# Power.net
KiCad netlist of a schematic drawn in Altium Designer
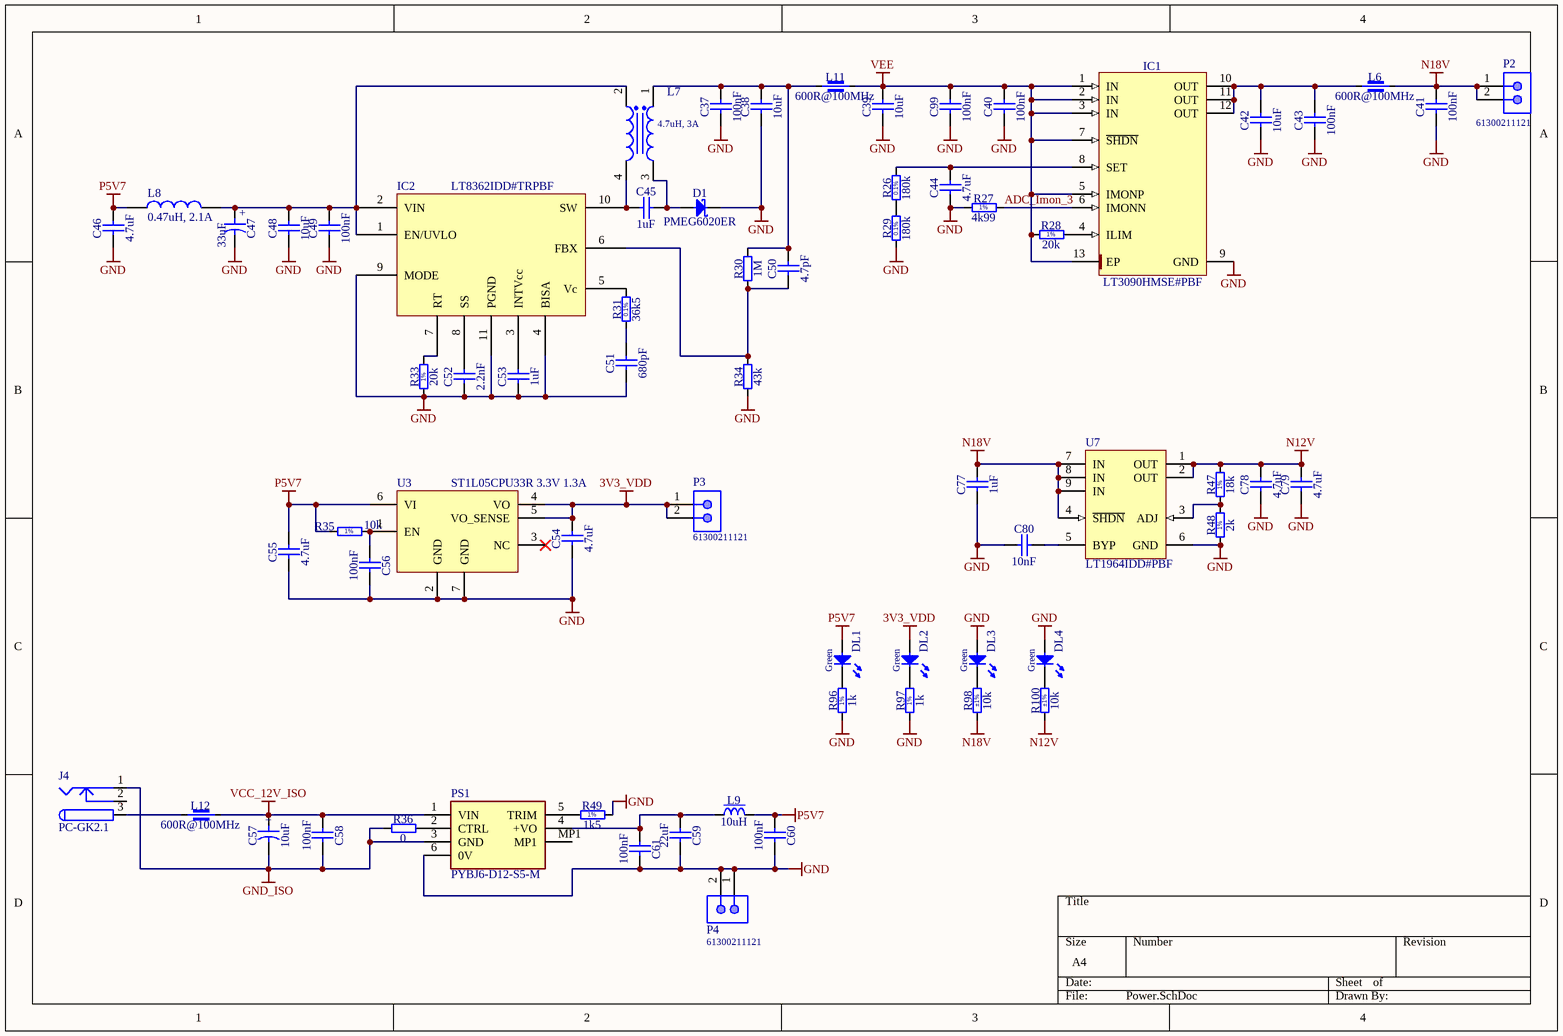
[diagram p0: Power.SchDoc]

(export (version "E")
  (design (tool "Eeschema 10.0.6"))
  (components
    (comp (ref "C37")
      (value "100nF")
      (footprint "CAPC1608X87N")
      (description "Non-polarised capacitor")
      (fields
        (field (name "PART NUMBER") "CC0603_100NF_50V_10%_X5R")
        (field (name "VOLTAGE") "50V")
        (field (name "AUTHOR") "CERN DEM MR")
      )
      (libsource (lib "Capacitors") (part "Capacitor - non polarized"))
    )
    (comp (ref "C38")
      (value "10uF")
      (footprint "CAPC3216X190N")
      (description "Non-polarised capacitor")
      (fields
        (field (name "PART NUMBER") "CC1206_10UF_35V_10%_X7R_YUDEN_GMJ316BB7106KLHT")
        (field (name "VOLTAGE") "35V")
        (field (name "AUTHOR") "CERN DEM BC")
      )
      (libsource (lib "Capacitors") (part "Capacitor - non polarized"))
    )
    (comp (ref "C39")
      (value "10uF")
      (footprint "CAPC3216X190N")
      (description "Non-polarised capacitor")
      (fields
        (field (name "PART NUMBER") "CC1206_10UF_35V_10%_X7R_YUDEN_GMJ316BB7106KLHT")
        (field (name "VOLTAGE") "35V")
        (field (name "AUTHOR") "CERN DEM BC")
      )
      (libsource (lib "Capacitors") (part "Capacitor - non polarized"))
    )
    (comp (ref "C40")
      (value "100nF")
      (footprint "CAPC1608X87N")
      (description "Non-polarised capacitor")
      (fields
        (field (name "PART NUMBER") "CC0603_100NF_50V_10%_X5R")
        (field (name "VOLTAGE") "50V")
        (field (name "AUTHOR") "CERN DEM MR")
      )
      (libsource (lib "Capacitors") (part "Capacitor - non polarized"))
    )
    (comp (ref "C41")
      (value "100nF")
      (footprint "CAPC1608X87N")
      (description "Non-polarised capacitor")
      (fields
        (field (name "PART NUMBER") "CC0603_100NF_50V_10%_X5R")
        (field (name "VOLTAGE") "50V")
        (field (name "AUTHOR") "CERN DEM MR")
      )
      (libsource (lib "Capacitors") (part "Capacitor - non polarized"))
    )
    (comp (ref "C42")
      (value "10uF")
      (footprint "CAPC3216X190N")
      (description "Non-polarised capacitor")
      (fields
        (field (name "PART NUMBER") "CC1206_10UF_35V_10%_X7R_YUDEN_GMJ316BB7106KLHT")
        (field (name "VOLTAGE") "35V")
        (field (name "AUTHOR") "CERN DEM BC")
      )
      (libsource (lib "Capacitors") (part "Capacitor - non polarized"))
    )
    (comp (ref "C43")
      (value "100nF")
      (footprint "CAPC1608X87N")
      (description "Non-polarised capacitor")
      (fields
        (field (name "PART NUMBER") "CC0603_100NF_50V_10%_X5R")
        (field (name "VOLTAGE") "50V")
        (field (name "AUTHOR") "CERN DEM MR")
      )
      (libsource (lib "Capacitors") (part "Capacitor - non polarized"))
    )
    (comp (ref "C44")
      (value "4.7uF")
      (footprint "CAPC1608X90N")
      (description "Non-polarised capacitor")
      (fields
        (field (name "PART NUMBER") "CC0603_4.7UF_25V_10%_X5R")
        (field (name "VOLTAGE") "25V")
        (field (name "AUTHOR") "CERN DEM JLC")
      )
      (libsource (lib "Capacitors") (part "Capacitor - non polarized"))
    )
    (comp (ref "C45")
      (value "1uF")
      (footprint "CAPC3216X140N")
      (description "Non-polarised capacitor")
      (fields
        (field (name "PART NUMBER") "CC1206_1UF_100V_10%_X7R")
        (field (name "VOLTAGE") "100V")
        (field (name "AUTHOR") "CERN DEM BC")
      )
      (libsource (lib "Capacitors") (part "Capacitor - non polarized"))
    )
    (comp (ref "C46")
      (value "4.7uF")
      (footprint "CAPC1608X90N")
      (description "Non-polarised capacitor")
      (fields
        (field (name "PART NUMBER") "CC0603_4.7UF_25V_10%_X5R")
        (field (name "VOLTAGE") "25V")
        (field (name "AUTHOR") "CERN DEM JLC")
      )
      (libsource (lib "Capacitors") (part "Capacitor - non polarized"))
    )
    (comp (ref "C47")
      (value "33uF")
      (footprint "CAPAE660X540N")
      (description "Polarised capacitor")
      (fields
        (field (name "PART NUMBER") "CAE660-540_33UF_35V_20%")
        (field (name "VOLTAGE") "35V")
        (field (name "AUTHOR") "CERN DEM JLC")
      )
      (libsource (lib "") (part "Capacitor - polarized_1"))
    )
    (comp (ref "C48")
      (value "10uF")
      (footprint "CAPC3216X190N")
      (description "Non-polarised capacitor")
      (fields
        (field (name "PART NUMBER") "CC1206_10UF_35V_10%_X7R_YUDEN_GMJ316BB7106KLHT")
        (field (name "VOLTAGE") "35V")
        (field (name "AUTHOR") "CERN DEM BC")
      )
      (libsource (lib "Capacitors") (part "Capacitor - non polarized"))
    )
    (comp (ref "C49")
      (value "100nF")
      (footprint "CAPC1608X87N")
      (description "Non-polarised capacitor")
      (fields
        (field (name "PART NUMBER") "CC0603_100NF_50V_10%_X5R")
        (field (name "VOLTAGE") "50V")
        (field (name "AUTHOR") "CERN DEM MR")
      )
      (libsource (lib "Capacitors") (part "Capacitor - non polarized"))
    )
    (comp (ref "C50")
      (value "4.7pF")
      (footprint "CAPC1005X55N")
      (description "Non-polarised capacitor")
      (fields
        (field (name "PART NUMBER") "CC0402_4.7PF_50V_0.25PF_C0G")
        (field (name "VOLTAGE") "50V")
        (field (name "AUTHOR") "CERN DEM JLC")
      )
      (libsource (lib "Capacitors") (part "Capacitor - non polarized"))
    )
    (comp (ref "C51")
      (value "680pF")
      (footprint "CAPC1005X55N")
      (description "Non-polarised capacitor")
      (fields
        (field (name "PART NUMBER") "CC0402_680PF_50V_5%_X7R")
        (field (name "VOLTAGE") "50V")
        (field (name "AUTHOR") "CERN DEM JLC")
      )
      (libsource (lib "Capacitors") (part "Capacitor - non polarized"))
    )
    (comp (ref "C52")
      (value "2.2nF")
      (footprint "CAPC1005X55N")
      (description "Non-polarised capacitor")
      (fields
        (field (name "PART NUMBER") "CC0402_2.2NF_50V_10%_X7R")
        (field (name "VOLTAGE") "50V")
        (field (name "AUTHOR") "CERN DEM JLC")
      )
      (libsource (lib "Capacitors") (part "Capacitor - non polarized"))
    )
    (comp (ref "C53")
      (value "1uF")
      (footprint "CAPC1608X87N")
      (description "Non-polarised capacitor")
      (fields
        (field (name "PART NUMBER") "CC0603_1UF_16V_10%_X7R")
        (field (name "VOLTAGE") "16V")
        (field (name "AUTHOR") "CERN DEM JLC")
      )
      (libsource (lib "Capacitors") (part "Capacitor - non polarized"))
    )
    (comp (ref "C54")
      (value "4.7uF")
      (footprint "CAPC1709X95N")
      (description "Non-polarised capacitor")
      (fields
        (field (name "PART NUMBER") "CC0603_4.7UF_16V_10%_X5R")
        (field (name "VOLTAGE") "16V")
        (field (name "AUTHOR") "CERN DEM JLC")
      )
      (libsource (lib "Capacitors") (part "Capacitor - non polarized"))
    )
    (comp (ref "C55")
      (value "4.7uF")
      (footprint "CAPC1709X95N")
      (description "Non-polarised capacitor")
      (fields
        (field (name "PART NUMBER") "CC0603_4.7UF_16V_10%_X5R")
        (field (name "VOLTAGE") "16V")
        (field (name "AUTHOR") "CERN DEM JLC")
      )
      (libsource (lib "Capacitors") (part "Capacitor - non polarized"))
    )
    (comp (ref "C56")
      (value "100nF")
      (footprint "CAPC1005X55N")
      (description "Non-polarised capacitor")
      (fields
        (field (name "PART NUMBER") "CC0402_100NF_16V_10%_X5R")
        (field (name "VOLTAGE") "16V")
        (field (name "AUTHOR") "CERN DEM JLC")
      )
      (libsource (lib "Capacitors") (part "Capacitor - non polarized"))
    )
    (comp (ref "C57")
      (value "10uF")
      (footprint "CAPAE430X540N")
      (description "Polarised capacitor")
      (fields
        (field (name "PART NUMBER") "CAE430-540_10UF_16V_20%")
        (field (name "VOLTAGE") "16V")
        (field (name "AUTHOR") "CERN DEM JLC")
      )
      (libsource (lib "Capacitors") (part "Capacitor - polarized"))
    )
    (comp (ref "C58")
      (value "100nF")
      (footprint "CAPC1005X55N")
      (description "Non-polarised capacitor")
      (fields
        (field (name "PART NUMBER") "CC0402_100NF_16V_10%_X5R")
        (field (name "VOLTAGE") "16V")
        (field (name "AUTHOR") "CERN DEM JLC")
      )
      (libsource (lib "Capacitors") (part "Capacitor - non polarized"))
    )
    (comp (ref "C59")
      (value "22uF")
      (footprint "CAPC2012X135N")
      (description "Non-polarised capacitor")
      (fields
        (field (name "PART NUMBER") "CC0805_22UF_16V_10%_X5R")
        (field (name "VOLTAGE") "16V")
        (field (name "AUTHOR") "CERN DEM JLC")
      )
      (libsource (lib "Capacitors") (part "Capacitor - non polarized"))
    )
    (comp (ref "C60")
      (value "100nF")
      (footprint "CAPC1005X55N")
      (description "Non-polarised capacitor")
      (fields
        (field (name "PART NUMBER") "CC0402_100NF_16V_10%_X5R")
        (field (name "VOLTAGE") "16V")
        (field (name "AUTHOR") "CERN DEM JLC")
      )
      (libsource (lib "Capacitors") (part "Capacitor - non polarized"))
    )
    (comp (ref "C61")
      (value "100nF")
      (footprint "CAPC1005X55N")
      (description "Non-polarised capacitor")
      (fields
        (field (name "PART NUMBER") "CC0402_100NF_16V_10%_X5R")
        (field (name "VOLTAGE") "16V")
        (field (name "AUTHOR") "CERN DEM JLC")
      )
      (libsource (lib "Capacitors") (part "Capacitor - non polarized"))
    )
    (comp (ref "C77")
      (value "1uF")
      (footprint "CAPC1608X87N")
      (description "Non-polarised capacitor")
      (fields
        (field (name "PART NUMBER") "CC0603_1UF_25V_10%_X7R")
        (field (name "VOLTAGE") "25V")
        (field (name "AUTHOR") "CERN DEM JLC")
      )
      (libsource (lib "Capacitors") (part "Capacitor - non polarized"))
    )
    (comp (ref "C78")
      (value "4.7uF")
      (footprint "CAPC1709X95N")
      (description "Non-polarised capacitor")
      (fields
        (field (name "PART NUMBER") "CC0603_4.7UF_16V_10%_X5R")
        (field (name "VOLTAGE") "16V")
        (field (name "AUTHOR") "CERN DEM JLC")
      )
      (libsource (lib "Capacitors") (part "Capacitor - non polarized"))
    )
    (comp (ref "C79")
      (value "4.7uF")
      (footprint "CAPC1709X95N")
      (description "Non-polarised capacitor")
      (fields
        (field (name "PART NUMBER") "CC0603_4.7UF_16V_10%_X5R")
        (field (name "VOLTAGE") "16V")
        (field (name "AUTHOR") "CERN DEM JLC")
      )
      (libsource (lib "Capacitors") (part "Capacitor - non polarized"))
    )
    (comp (ref "C80")
      (value "10nF")
      (footprint "CAPC1005X55N")
      (description "Non-polarised capacitor")
      (fields
        (field (name "PART NUMBER") "CC0402_10NF_16V_10%_X7R")
        (field (name "VOLTAGE") "16V")
        (field (name "AUTHOR") "CERN DEM JLC")
      )
      (libsource (lib "Capacitors") (part "Capacitor - non polarized"))
    )
    (comp (ref "C99")
      (value "100nF")
      (footprint "CAPC1608X87N")
      (description "Non-polarised capacitor")
      (fields
        (field (name "PART NUMBER") "CC0603_100NF_50V_10%_X5R")
        (field (name "VOLTAGE") "50V")
        (field (name "AUTHOR") "CERN DEM MR")
      )
      (libsource (lib "Capacitors") (part "Capacitor - non polarized"))
    )
    (comp (ref "D1")
      (value "PMEG6020ER")
      (footprint "SODFL3517X110N")
      (description "Schottky Diode")
      (fields
        (field (name "VOLTAGE") "60V")
        (field (name "POWER") "2A")
        (field (name "AUTHOR") "CERN DEM JMW")
      )
      (libsource (lib "ICs And Semiconductors") (part "Diode Schottky"))
    )
    (comp (ref "DL1")
      (value "Green")
      (footprint "LED_OSRAM_LGL29K")
      (description "LED Green 1C 2A")
      (fields
        (field (name "PART NUMBER") "LED_OSRAM_LG L29K-G2J1-24-Z")
        (field (name "MANUFACTURER") "OSRAM")
        (field (name "AUTHOR") "CERN DEM JLC")
      )
      (libsource (lib "ICs And Semiconductors") (part "LED Green 1C 2A"))
    )
    (comp (ref "DL2")
      (value "Green")
      (footprint "LED_OSRAM_LGL29K")
      (description "LED Green 1C 2A")
      (fields
        (field (name "PART NUMBER") "LED_OSRAM_LG L29K-G2J1-24-Z")
        (field (name "MANUFACTURER") "OSRAM")
        (field (name "AUTHOR") "CERN DEM JLC")
      )
      (libsource (lib "ICs And Semiconductors") (part "LED Green 1C 2A"))
    )
    (comp (ref "DL3")
      (value "Green")
      (footprint "LED_OSRAM_LGL29K")
      (description "LED Green 1C 2A")
      (fields
        (field (name "PART NUMBER") "LED_OSRAM_LG L29K-G2J1-24-Z")
        (field (name "MANUFACTURER") "OSRAM")
        (field (name "AUTHOR") "CERN DEM JLC")
      )
      (libsource (lib "ICs And Semiconductors") (part "LED Green 1C 2A"))
    )
    (comp (ref "DL4")
      (value "Green")
      (footprint "LED_OSRAM_LGL29K")
      (description "LED Green 1C 2A")
      (fields
        (field (name "PART NUMBER") "LED_OSRAM_LG L29K-G2J1-24-Z")
        (field (name "MANUFACTURER") "OSRAM")
        (field (name "AUTHOR") "CERN DEM JLC")
      )
      (libsource (lib "ICs And Semiconductors") (part "LED Green 1C 2A"))
    )
    (comp (ref "IC1")
      (value "LT3090HMSE#PBF")
      (footprint "SOP65P490X110-13N-R175X294")
      (description "–36V, 600mA Negative Linear Regulator with Programmable Current Limit")
      (fields (field (name "MANUFACTURER") "LINEAR TECHNOLOGY") (field (name "AUTHOR") "CERN DEM JLC"))
      (libsource (lib "ICs And Semiconductors") (part "LT3090HMSE#PBF"))
    )
    (comp (ref "IC2")
      (value "LT8362IDD#TRPBF")
      (footprint "SON50P300X300X80-11N-R160X240")
      (libsource (lib "MG_lib") (part "LT8362IDD#TRPBF"))
    )
    (comp (ref "J4")
      (value "PC-GK2.1")
      (footprint "DC2020")
      (description "Low Voltage Power Supply Connector (maritex)")
      (fields (field (name "PUBLISHER") "Altium Limited"))
      (libsource (lib "LIBRARY_SCH") (part "CON_DC_JACK_TH"))
    )
    (comp (ref "L6")
      (value "600R@100MHz")
      (footprint "INDC2012X110N")
      (fields
        (field (name "PART NUMBER") "IND0805_WURTH_742792040")
        (field (name "POWER") "2A")
        (field (name "TOLERANCE") "±25%")
        (field (name "AUTHOR") "CERN DEM JLC")
      )
      (libsource (lib "Inductors & Transformers") (part "Ferrite Bead"))
    )
    (comp (ref "L7")
      (value "4.7uH, 3A")
      (footprint "WE-DD_1260")
      (description "WE-DD SMT Shielded Coupled Inductor, size 1260, 4.7uH, 3A")
      (fields
        (field (name "MANUFACTURER") "Wurth Elektronik")
        (field (name "MANUFACTURER PART NUMBER") "744871004")
      )
      (libsource (lib "744871470_Altium_WE-DD_rev20a") (part "744871004"))
    )
    (comp (ref "L8")
      (value "0.47uH, 2.1A")
      (footprint "WE-PMI_0806_H1")
      (description "WE-PMI Power Multilayer Inductor, size 0806, 0.47uH, 2.1A")
      (fields
        (field (name "MANUFACTURER") "Wurth Elektronik")
        (field (name "MANUFACTURER PART NUMBER") "74479876147")
      )
      (libsource (lib "Altium_WE-PMI_rev20a") (part "74479876147"))
    )
    (comp (ref "L9")
      (value "10uH")
      (footprint "IND_MURATA-PS_8400")
      (description "Inductor With Core")
      (fields
        (field (name "PART NUMBER") "IND_10UH_10%_MURATA-PS_8400")
        (field (name "POWER") "950mA")
        (field (name "AUTHOR") "CERN DEM JLC")
      )
      (libsource (lib "Inductors & Transformers") (part "Inductor With Magnetic core"))
    )
    (comp (ref "L11")
      (value "600R@100MHz")
      (footprint "INDC2012X110N")
      (fields
        (field (name "PART NUMBER") "IND0805_WURTH_742792040")
        (field (name "POWER") "2A")
        (field (name "TOLERANCE") "±25%")
        (field (name "AUTHOR") "CERN DEM JLC")
      )
      (libsource (lib "Inductors & Transformers") (part "Ferrite Bead"))
    )
    (comp (ref "L12")
      (value "600R@100MHz")
      (footprint "INDC2012X110N")
      (fields
        (field (name "PART NUMBER") "IND0805_WURTH_742792040")
        (field (name "POWER") "2A")
        (field (name "TOLERANCE") "±25%")
        (field (name "AUTHOR") "CERN DEM JLC")
      )
      (libsource (lib "Inductors & Transformers") (part "Ferrite Bead"))
    )
    (comp (ref "P2")
      (value "61300211121")
      (footprint "61300211121")
      (description "WR-PHD Pin Header, THT, pitch 2.54mm, Single Row, Vertical, 2p")
      (fields (field (name "MANUFACTURER") "Wurth Elektronik"))
      (libsource (lib "o155175v243 Altium_WR-PHD (rev20a)") (part "61300211121"))
    )
    (comp (ref "P3")
      (value "61300211121")
      (footprint "61300211121")
      (description "WR-PHD Pin Header, THT, pitch 2.54mm, Single Row, Vertical, 2p")
      (fields (field (name "MANUFACTURER") "Wurth Elektronik"))
      (libsource (lib "o155175v243 Altium_WR-PHD (rev20a)") (part "61300211121"))
    )
    (comp (ref "P4")
      (value "61300211121")
      (footprint "61300211121")
      (description "WR-PHD Pin Header, THT, pitch 2.54mm, Single Row, Vertical, 2p")
      (fields (field (name "MANUFACTURER") "Wurth Elektronik"))
      (libsource (lib "o155175v243 Altium_WR-PHD (rev20a)") (part "61300211121"))
    )
    (comp (ref "PS1")
      (value "PYBJ6-D12-S5-M")
      (footprint "PYBJ6D12S12M")
      (description "Power Supply")
      (fields (field (name "MANUFACTURER_PART_NUMBER") "PYBJ6-D12-S12-M"))
      (libsource (lib "*") (part "PYBJ6-D12-S12-M"))
    )
    (comp (ref "R26")
      (value "180k")
      (footprint "RESC3216X65N")
      (description "Resistor - 0.1%")
      (fields
        (field (name "PART NUMBER") "R1206_180K_0.1%_0.25W_25PPM")
        (field (name "POWER") "0.25W")
        (field (name "AUTHOR") "CERN DEM JLC")
      )
      (libsource (lib "Resistors") (part "Resistor - 0.1%"))
    )
    (comp (ref "R27")
      (value "4k99")
      (footprint "RESC1608X55N")
      (description "Resistor - 1%")
      (fields
        (field (name "PART NUMBER") "R0603_4K99_1%_0.063W_50PPM")
        (field (name "POWER") "0.063W")
        (field (name "AUTHOR") "CERN DEM JLC")
      )
      (libsource (lib "Resistors") (part "Resistor - 1%"))
    )
    (comp (ref "R28")
      (value "20k")
      (footprint "RESC1005X40N")
      (description "Resistor - 1%")
      (fields
        (field (name "PART NUMBER") "R0402_20K_1%_0.0625W_100PPM")
        (field (name "POWER") "0.0625W")
        (field (name "AUTHOR") "CERN DEM JLC")
      )
      (libsource (lib "") (part "Resistor - 1%_1"))
    )
    (comp (ref "R29")
      (value "180k")
      (footprint "RESC3216X65N")
      (description "Resistor - 0.1%")
      (fields
        (field (name "PART NUMBER") "R1206_180K_0.1%_0.25W_25PPM")
        (field (name "POWER") "0.25W")
        (field (name "AUTHOR") "CERN DEM JLC")
      )
      (libsource (lib "Resistors") (part "Resistor - 0.1%"))
    )
    (comp (ref "R30")
      (value "1M")
      (footprint "RESC1005X40N")
      (description "Resistor - 1%")
      (fields
        (field (name "PART NUMBER") "R0402_1M_1%_0.0625W_100PPM")
        (field (name "POWER") "0.0625W")
        (field (name "AUTHOR") "CERN DEM JLC")
      )
      (libsource (lib "") (part "Resistor - 1%_1"))
    )
    (comp (ref "R31")
      (value "36k5")
      (footprint "RESC1608X55N")
      (description "Resistor - 0.1%")
      (fields
        (field (name "PART NUMBER") "R0603_36K5_0.1%_0.063W_10PPM")
        (field (name "POWER") "0.063W")
        (field (name "AUTHOR") "CERN DEM JLC")
      )
      (libsource (lib "Resistors") (part "Resistor - 0.1%"))
    )
    (comp (ref "R33")
      (value "20k")
      (footprint "RESC1005X40N")
      (description "Resistor - 1%")
      (fields
        (field (name "PART NUMBER") "R0402_20K_1%_0.0625W_100PPM")
        (field (name "POWER") "0.0625W")
        (field (name "AUTHOR") "CERN DEM JLC")
      )
      (libsource (lib "") (part "Resistor - 1%_1"))
    )
    (comp (ref "R34")
      (value "43k")
      (footprint "RESC1005X40N")
      (description "Resistor - 1%")
      (fields
        (field (name "PART NUMBER") "R0402_43K_1%_0.0625W_100PPM")
        (field (name "POWER") "0.0625W")
        (field (name "AUTHOR") "CERN DEM JLC")
      )
      (libsource (lib "") (part "Resistor - 1%_1"))
    )
    (comp (ref "R35")
      (value "10k")
      (footprint "RESC1005X40N")
      (description "Resistor - 1%")
      (fields
        (field (name "PART NUMBER") "R0402_10K_1%_0.0625W_100PPM")
        (field (name "POWER") "0.0625W")
        (field (name "AUTHOR") "CERN DEM JLC")
      )
      (libsource (lib "") (part "Resistor - 1%_1"))
    )
    (comp (ref "R36")
      (value "0")
      (footprint "RESC1608X55N")
      (description "Resistor")
      (fields
        (field (name "PART NUMBER") "R0603_0R_JUMPER")
        (field (name "MANUFACTURER") "GENERIC")
        (field (name "AUTHOR") "CERN DEM JLC")
      )
      (libsource (lib "Resistors") (part "Resistor"))
    )
    (comp (ref "R47")
      (value "18k")
      (footprint "RESC1005X40N")
      (description "Resistor - 1%")
      (fields
        (field (name "PART NUMBER") "R0402_18K_1%_0.0625W_100PPM")
        (field (name "POWER") "0.0625W")
        (field (name "AUTHOR") "CERN DEM JLC")
      )
      (libsource (lib "") (part "Resistor - 1%_1"))
    )
    (comp (ref "R48")
      (value "2k")
      (footprint "RESC1005X40N")
      (description "Resistor - 1%")
      (fields
        (field (name "PART NUMBER") "R0402_2K_1%_0.0625W_100PPM")
        (field (name "POWER") "0.0625W")
        (field (name "AUTHOR") "CERN DEM JLC")
      )
      (libsource (lib "") (part "Resistor - 1%_1"))
    )
    (comp (ref "R49")
      (value "1k5")
      (footprint "RESC1005X40N")
      (description "Resistor - 1%")
      (fields
        (field (name "PART NUMBER") "R0402_1K5_1%_0.0625W_100PPM")
        (field (name "POWER") "0.0625W")
        (field (name "AUTHOR") "CERN DEM JLC")
      )
      (libsource (lib "") (part "Resistor - 1%_1"))
    )
    (comp (ref "R96")
      (value "1k")
      (footprint "RESC1005X40N")
      (description "Resistor - 1%")
      (fields
        (field (name "PART NUMBER") "R0402_1K_1%_0.0625W_100PPM")
        (field (name "POWER") "0.0625W")
        (field (name "AUTHOR") "CERN DEM JLC")
      )
      (libsource (lib "") (part "Resistor - 1%_1"))
    )
    (comp (ref "R97")
      (value "1k")
      (footprint "RESC1005X40N")
      (description "Resistor - 1%")
      (fields
        (field (name "PART NUMBER") "R0402_1K_1%_0.0625W_100PPM")
        (field (name "POWER") "0.0625W")
        (field (name "AUTHOR") "CERN DEM JLC")
      )
      (libsource (lib "") (part "Resistor - 1%_1"))
    )
    (comp (ref "R98")
      (value "10k")
      (footprint "RESC1005X40N")
      (description "Resistor - 1%")
      (fields
        (field (name "TOLERANCE") "±1%")
        (field (name "PART NUMBER") "R0402_10K_1%_0.0625W_100PPM")
        (field (name "POWER") "0.0625W")
        (field (name "AUTHOR") "CERN DEM JLC")
      )
      (libsource (lib "") (part "Resistor - 1%_1"))
    )
    (comp (ref "R100")
      (value "10k")
      (footprint "RESC1005X40N")
      (description "Resistor - 1%")
      (fields
        (field (name "TOLERANCE") "±1%")
        (field (name "PART NUMBER") "R0402_10K_1%_0.0625W_100PPM")
        (field (name "POWER") "0.0625W")
        (field (name "AUTHOR") "CERN DEM JLC")
      )
      (libsource (lib "") (part "Resistor - 1%_1"))
    )
    (comp (ref "U3")
      (value "ST1L05CPU33R 3.3V 1.3A")
      (footprint "SON95P300X300X80-7N-R160X240")
      (description "LDO, 3.3V, 1.3A, Very low quiescent current BiCMOS voltage regulator")
      (fields
        (field (name "INTERNAL_PART_NUMBER") "MCD-01025")
        (field (name "MANUFACTURER_PART_NUMBER") "ST1L05CPU33R")
        (field (name "PROVIDED_BY") "SUBCO with ST control")
      )
      (libsource (lib "MCD_PARTS_database") (part "ST1L05CPU33R"))
    )
    (comp (ref "U7")
      (value "LT1964IDD#PBF")
      (footprint "LT-DD-8_V")
      (fields (field (name "MANUFACTURER") "Linear Technology"))
      (libsource (lib "Altium Content Vault") (part "LT-LT1964-DD-8"))
    )
  )
  (nets
    (net (code "1") (name "/ADC_Imon_3") (class "Default")
      (node (ref "IC1") (pin "6") (pinfunction "IMONN_6") (pintype "input"))
      (node (ref "R27") (pin "2") (pinfunction "2_2") (pintype "passive"))
    )
    (net (code "2") (name "3V3_VDD") (class "Default")
      (node (ref "C54") (pin "2") (pinfunction "2_2") (pintype "passive"))
      (node (ref "DL2") (pin "2") (pinfunction "A_2") (pintype "passive"))
      (node (ref "P3") (pin "1") (pinfunction "1_1") (pintype "passive"))
      (node (ref "P3") (pin "2") (pinfunction "2_2") (pintype "passive"))
      (node (ref "U3") (pin "4") (pinfunction "VO_4") (pintype "passive"))
      (node (ref "U3") (pin "5") (pinfunction "VO_SENSE_5") (pintype "passive"))
    )
    (net (code "3") (name "GND") (class "Default")
      (node (ref "C37") (pin "1") (pinfunction "1_1") (pintype "passive"))
      (node (ref "C38") (pin "1") (pinfunction "1_1") (pintype "passive"))
      (node (ref "C39") (pin "1") (pinfunction "1_1") (pintype "passive"))
      (node (ref "C40") (pin "1") (pinfunction "1_1") (pintype "passive"))
      (node (ref "C41") (pin "1") (pinfunction "1_1") (pintype "passive"))
      (node (ref "C42") (pin "1") (pinfunction "1_1") (pintype "passive"))
      (node (ref "C43") (pin "1") (pinfunction "1_1") (pintype "passive"))
      (node (ref "C44") (pin "1") (pinfunction "1_1") (pintype "passive"))
      (node (ref "C46") (pin "1") (pinfunction "1_1") (pintype "passive"))
      (node (ref "C47") (pin "2") (pinfunction "2_2") (pintype "passive"))
      (node (ref "C48") (pin "1") (pinfunction "1_1") (pintype "passive"))
      (node (ref "C49") (pin "1") (pinfunction "1_1") (pintype "passive"))
      (node (ref "C51") (pin "1") (pinfunction "1_1") (pintype "passive"))
      (node (ref "C52") (pin "1") (pinfunction "1_1") (pintype "passive"))
      (node (ref "C53") (pin "1") (pinfunction "1_1") (pintype "passive"))
      (node (ref "C54") (pin "1") (pinfunction "1_1") (pintype "passive"))
      (node (ref "C55") (pin "1") (pinfunction "1_1") (pintype "passive"))
      (node (ref "C56") (pin "1") (pinfunction "1_1") (pintype "passive"))
      (node (ref "C59") (pin "1") (pinfunction "1_1") (pintype "passive"))
      (node (ref "C60") (pin "1") (pinfunction "1_1") (pintype "passive"))
      (node (ref "C61") (pin "1") (pinfunction "1_1") (pintype "passive"))
      (node (ref "C77") (pin "1") (pinfunction "1_1") (pintype "passive"))
      (node (ref "C78") (pin "1") (pinfunction "1_1") (pintype "passive"))
      (node (ref "C79") (pin "1") (pinfunction "1_1") (pintype "passive"))
      (node (ref "C80") (pin "1") (pinfunction "1_1") (pintype "passive"))
      (node (ref "C99") (pin "1") (pinfunction "1_1") (pintype "passive"))
      (node (ref "D1") (pin "1") (pinfunction "C_1") (pintype "passive"))
      (node (ref "DL3") (pin "2") (pinfunction "A_2") (pintype "passive"))
      (node (ref "DL4") (pin "2") (pinfunction "A_2") (pintype "passive"))
      (node (ref "IC1") (pin "9") (pinfunction "GND_9") (pintype "power_in"))
      (node (ref "IC2") (pin "11") (pinfunction "PGND_11") (pintype "passive"))
      (node (ref "IC2") (pin "4") (pinfunction "BISA_4") (pintype "passive"))
      (node (ref "IC2") (pin "9") (pinfunction "MODE_9") (pintype "passive"))
      (node (ref "P4") (pin "1") (pinfunction "1_1") (pintype "passive"))
      (node (ref "P4") (pin "2") (pinfunction "2_2") (pintype "passive"))
      (node (ref "PS1") (pin "6") (pinfunction "0V_6") (pintype "passive"))
      (node (ref "R27") (pin "1") (pinfunction "1_1") (pintype "passive"))
      (node (ref "R29") (pin "1") (pinfunction "1_1") (pintype "passive"))
      (node (ref "R33") (pin "1") (pinfunction "1_1") (pintype "passive"))
      (node (ref "R34") (pin "1") (pinfunction "1_1") (pintype "passive"))
      (node (ref "R48") (pin "1") (pinfunction "1_1") (pintype "passive"))
      (node (ref "R49") (pin "2") (pinfunction "2_2") (pintype "passive"))
      (node (ref "R96") (pin "1") (pinfunction "1_1") (pintype "passive"))
      (node (ref "R97") (pin "1") (pinfunction "1_1") (pintype "passive"))
      (node (ref "U3") (pin "2") (pinfunction "GND_2") (pintype "passive"))
      (node (ref "U3") (pin "7") (pinfunction "GND_7") (pintype "passive"))
      (node (ref "U7") (pin "6") (pinfunction "GND_6") (pintype "power_in"))
    )
    (net (code "4") (name "GND_ISO") (class "Default")
      (node (ref "C57") (pin "2") (pinfunction "2_2") (pintype "passive"))
      (node (ref "C58") (pin "1") (pinfunction "1_1") (pintype "passive"))
      (node (ref "J4") (pin "1") (pintype "power_in"))
      (node (ref "PS1") (pin "3") (pinfunction "GND_3") (pintype "passive"))
      (node (ref "R36") (pin "2") (pinfunction "2_2") (pintype "passive"))
    )
    (net (code "5") (name "N12V") (class "Default")
      (node (ref "C78") (pin "2") (pinfunction "2_2") (pintype "passive"))
      (node (ref "C79") (pin "2") (pinfunction "2_2") (pintype "passive"))
      (node (ref "R100") (pin "1") (pinfunction "1_1") (pintype "passive"))
      (node (ref "R47") (pin "2") (pinfunction "2_2") (pintype "passive"))
      (node (ref "U7") (pin "1") (pinfunction "OUT_1") (pintype "power_in"))
      (node (ref "U7") (pin "2") (pinfunction "OUT_2") (pintype "power_in"))
    )
    (net (code "6") (name "N18V") (class "Default")
      (node (ref "C41") (pin "2") (pinfunction "2_2") (pintype "passive"))
      (node (ref "C77") (pin "2") (pinfunction "2_2") (pintype "passive"))
      (node (ref "L6") (pin "2") (pinfunction "2_2") (pintype "passive"))
      (node (ref "P2") (pin "1") (pinfunction "1_1") (pintype "passive"))
      (node (ref "P2") (pin "2") (pinfunction "2_2") (pintype "passive"))
      (node (ref "R98") (pin "1") (pinfunction "1_1") (pintype "passive"))
      (node (ref "U7") (pin "4") (pinfunction "~{SHDN}_4") (pintype "input"))
      (node (ref "U7") (pin "7") (pinfunction "IN_7") (pintype "power_in"))
      (node (ref "U7") (pin "8") (pinfunction "IN_8") (pintype "power_in"))
      (node (ref "U7") (pin "9") (pinfunction "IN_9") (pintype "power_in"))
    )
    (net (code "7") (name "Net-(C37-Pad2)") (class "Default")
      (node (ref "C37") (pin "2") (pinfunction "2_2") (pintype "passive"))
      (node (ref "C38") (pin "2") (pinfunction "2_2") (pintype "passive"))
      (node (ref "C50") (pin "2") (pinfunction "2_2") (pintype "passive"))
      (node (ref "L11") (pin "1") (pinfunction "1_1") (pintype "passive"))
      (node (ref "L7") (pin "1") (pinfunction "1_1") (pintype "passive"))
      (node (ref "R30") (pin "2") (pinfunction "2_2") (pintype "passive"))
    )
    (net (code "8") (name "Net-(C42-Pad2)") (class "Default")
      (node (ref "C42") (pin "2") (pinfunction "2_2") (pintype "passive"))
      (node (ref "C43") (pin "2") (pinfunction "2_2") (pintype "passive"))
      (node (ref "IC1") (pin "10") (pinfunction "OUT_10") (pintype "power_in"))
      (node (ref "IC1") (pin "11") (pinfunction "OUT_11") (pintype "power_in"))
      (node (ref "IC1") (pin "12") (pinfunction "OUT_12") (pintype "power_in"))
      (node (ref "L6") (pin "1") (pinfunction "1_1") (pintype "passive"))
    )
    (net (code "9") (name "Net-(C51-Pad2)") (class "Default")
      (node (ref "C51") (pin "2") (pinfunction "2_2") (pintype "passive"))
      (node (ref "R31") (pin "1") (pinfunction "1_1") (pintype "passive"))
    )
    (net (code "10") (name "Net-(D1-A)") (class "Default")
      (node (ref "C45") (pin "2") (pinfunction "2_2") (pintype "passive"))
      (node (ref "D1") (pin "2") (pinfunction "A_2") (pintype "passive"))
      (node (ref "L7") (pin "3") (pinfunction "3_3") (pintype "passive"))
    )
    (net (code "11") (name "Net-(DL1-C)") (class "Default")
      (node (ref "DL1") (pin "1") (pinfunction "C_1") (pintype "passive"))
      (node (ref "R96") (pin "2") (pinfunction "2_2") (pintype "passive"))
    )
    (net (code "12") (name "Net-(DL2-C)") (class "Default")
      (node (ref "DL2") (pin "1") (pinfunction "C_1") (pintype "passive"))
      (node (ref "R97") (pin "2") (pinfunction "2_2") (pintype "passive"))
    )
    (net (code "13") (name "Net-(DL3-C)") (class "Default")
      (node (ref "DL3") (pin "1") (pinfunction "C_1") (pintype "passive"))
      (node (ref "R98") (pin "2") (pinfunction "2_2") (pintype "passive"))
    )
    (net (code "14") (name "Net-(DL4-C)") (class "Default")
      (node (ref "DL4") (pin "1") (pinfunction "C_1") (pintype "passive"))
      (node (ref "R100") (pin "2") (pinfunction "2_2") (pintype "passive"))
    )
    (net (code "15") (name "Net-(IC1-ILIM)") (class "Default")
      (node (ref "IC1") (pin "4") (pinfunction "ILIM_4") (pintype "input"))
      (node (ref "R28") (pin "2") (pinfunction "2_2") (pintype "passive"))
    )
    (net (code "16") (name "Net-(IC1-SET)") (class "Default")
      (node (ref "C44") (pin "2") (pinfunction "2_2") (pintype "passive"))
      (node (ref "IC1") (pin "8") (pinfunction "SET_8") (pintype "input"))
      (node (ref "R26") (pin "2") (pinfunction "2_2") (pintype "passive"))
    )
    (net (code "17") (name "Net-(IC2-EN{slash}UVLO)") (class "Default")
      (node (ref "C47") (pin "1") (pinfunction "1_1") (pintype "passive"))
      (node (ref "C48") (pin "2") (pinfunction "2_2") (pintype "passive"))
      (node (ref "C49") (pin "2") (pinfunction "2_2") (pintype "passive"))
      (node (ref "IC2") (pin "1") (pinfunction "EN/UVLO_1") (pintype "passive"))
      (node (ref "IC2") (pin "2") (pinfunction "VIN_2") (pintype "passive"))
      (node (ref "L7") (pin "2") (pinfunction "2_2") (pintype "passive"))
      (node (ref "L8") (pin "2") (pinfunction "2_2") (pintype "passive"))
    )
    (net (code "18") (name "Net-(IC2-FBX)") (class "Default")
      (node (ref "C50") (pin "1") (pinfunction "1_1") (pintype "passive"))
      (node (ref "IC2") (pin "6") (pinfunction "FBX_6") (pintype "passive"))
      (node (ref "R30") (pin "1") (pinfunction "1_1") (pintype "passive"))
      (node (ref "R34") (pin "2") (pinfunction "2_2") (pintype "passive"))
    )
    (net (code "19") (name "Net-(IC2-INTVcc)") (class "Default")
      (node (ref "C53") (pin "2") (pinfunction "2_2") (pintype "passive"))
      (node (ref "IC2") (pin "3") (pinfunction "INTVcc_3") (pintype "passive"))
    )
    (net (code "20") (name "Net-(IC2-RT)") (class "Default")
      (node (ref "IC2") (pin "7") (pinfunction "RT_7") (pintype "passive"))
      (node (ref "R33") (pin "2") (pinfunction "2_2") (pintype "passive"))
    )
    (net (code "21") (name "Net-(IC2-SS)") (class "Default")
      (node (ref "C52") (pin "2") (pinfunction "2_2") (pintype "passive"))
      (node (ref "IC2") (pin "8") (pinfunction "SS_8") (pintype "passive"))
    )
    (net (code "22") (name "Net-(IC2-SW)") (class "Default")
      (node (ref "C45") (pin "1") (pinfunction "1_1") (pintype "passive"))
      (node (ref "IC2") (pin "10") (pinfunction "SW_10") (pintype "passive"))
      (node (ref "L7") (pin "4") (pinfunction "4_4") (pintype "passive"))
    )
    (net (code "23") (name "Net-(IC2-Vc)") (class "Default")
      (node (ref "IC2") (pin "5") (pinfunction "Vc_5") (pintype "passive"))
      (node (ref "R31") (pin "2") (pinfunction "2_2") (pintype "passive"))
    )
    (net (code "24") (name "Net-(J4-Pad3)") (class "Default")
      (node (ref "J4") (pin "3") (pintype "power_in"))
      (node (ref "L12") (pin "1") (pinfunction "1_1") (pintype "passive"))
    )
    (net (code "25") (name "Net-(PS1-+VO)") (class "Default")
      (node (ref "C59") (pin "2") (pinfunction "2_2") (pintype "passive"))
      (node (ref "C61") (pin "2") (pinfunction "2_2") (pintype "passive"))
      (node (ref "L9") (pin "2") (pinfunction "2_2") (pintype "passive"))
      (node (ref "PS1") (pin "4") (pinfunction "+VO_4") (pintype "passive"))
    )
    (net (code "26") (name "Net-(PS1-CTRL)") (class "Default")
      (node (ref "PS1") (pin "2") (pinfunction "CTRL_2") (pintype "passive"))
      (node (ref "R36") (pin "1") (pinfunction "1_1") (pintype "passive"))
    )
    (net (code "27") (name "Net-(PS1-TRIM)") (class "Default")
      (node (ref "PS1") (pin "5") (pinfunction "TRIM_5") (pintype "passive"))
      (node (ref "R49") (pin "1") (pinfunction "1_1") (pintype "passive"))
    )
    (net (code "28") (name "Net-(R26-Pad1)") (class "Default")
      (node (ref "R26") (pin "1") (pinfunction "1_1") (pintype "passive"))
      (node (ref "R29") (pin "2") (pinfunction "2_2") (pintype "passive"))
    )
    (net (code "29") (name "Net-(U3-EN)") (class "Default")
      (node (ref "C56") (pin "2") (pinfunction "2_2") (pintype "passive"))
      (node (ref "R35") (pin "2") (pinfunction "2_2") (pintype "passive"))
      (node (ref "U3") (pin "1") (pinfunction "EN_1") (pintype "passive"))
    )
    (net (code "30") (name "Net-(U7-ADJ)") (class "Default")
      (node (ref "R47") (pin "1") (pinfunction "1_1") (pintype "passive"))
      (node (ref "R48") (pin "2") (pinfunction "2_2") (pintype "passive"))
      (node (ref "U7") (pin "3") (pinfunction "ADJ_3") (pintype "input"))
    )
    (net (code "31") (name "Net-(U7-BYP)") (class "Default")
      (node (ref "C80") (pin "2") (pinfunction "2_2") (pintype "passive"))
      (node (ref "U7") (pin "5") (pinfunction "BYP_5") (pintype "passive"))
    )
    (net (code "32") (name "P5V7") (class "Default")
      (node (ref "C46") (pin "2") (pinfunction "2_2") (pintype "passive"))
      (node (ref "C55") (pin "2") (pinfunction "2_2") (pintype "passive"))
      (node (ref "C60") (pin "2") (pinfunction "2_2") (pintype "passive"))
      (node (ref "DL1") (pin "2") (pinfunction "A_2") (pintype "passive"))
      (node (ref "L8") (pin "1") (pinfunction "1_1") (pintype "passive"))
      (node (ref "L9") (pin "1") (pinfunction "1_1") (pintype "passive"))
      (node (ref "R35") (pin "1") (pinfunction "1_1") (pintype "passive"))
      (node (ref "U3") (pin "6") (pinfunction "VI_6") (pintype "passive"))
    )
    (net (code "33") (name "VCC_12V_ISO") (class "Default")
      (node (ref "C57") (pin "1") (pinfunction "1_1") (pintype "passive"))
      (node (ref "C58") (pin "2") (pinfunction "2_2") (pintype "passive"))
      (node (ref "L12") (pin "2") (pinfunction "2_2") (pintype "passive"))
      (node (ref "PS1") (pin "1") (pinfunction "VIN_1") (pintype "passive"))
    )
    (net (code "34") (name "VEE") (class "Default")
      (node (ref "C39") (pin "2") (pinfunction "2_2") (pintype "passive"))
      (node (ref "C40") (pin "2") (pinfunction "2_2") (pintype "passive"))
      (node (ref "C99") (pin "2") (pinfunction "2_2") (pintype "passive"))
      (node (ref "IC1") (pin "1") (pinfunction "IN_1") (pintype "input"))
      (node (ref "IC1") (pin "13") (pinfunction "EP_13") (pintype "power_in"))
      (node (ref "IC1") (pin "2") (pinfunction "IN_2") (pintype "input"))
      (node (ref "IC1") (pin "3") (pinfunction "IN_3") (pintype "input"))
      (node (ref "IC1") (pin "5") (pinfunction "IMONP_5") (pintype "input"))
      (node (ref "IC1") (pin "7") (pinfunction "~{SHDN}_7") (pintype "input"))
      (node (ref "L11") (pin "2") (pinfunction "2_2") (pintype "passive"))
      (node (ref "R28") (pin "1") (pinfunction "1_1") (pintype "passive"))
    )
    (net (code "35") (name "unconnected-(J4-Pad2)") (class "Default")
      (node (ref "J4") (pin "2") (pintype "power_in"))
    )
    (net (code "36") (name "unconnected-(PS1-PadMP1)") (class "Default")
      (node (ref "PS1") (pin "MP1") (pinfunction "MP1_MP1") (pintype "passive"))
    )
    (net (code "37") (name "unconnected-(U3-NC-Pad3)") (class "Default")
      (node (ref "U3") (pin "3") (pinfunction "NC_3") (pintype "passive+no_connect"))
    )
  )
)
